# motor_driver_current_sensor.net
KiCad netlist of a schematic drawn in Altium Designer
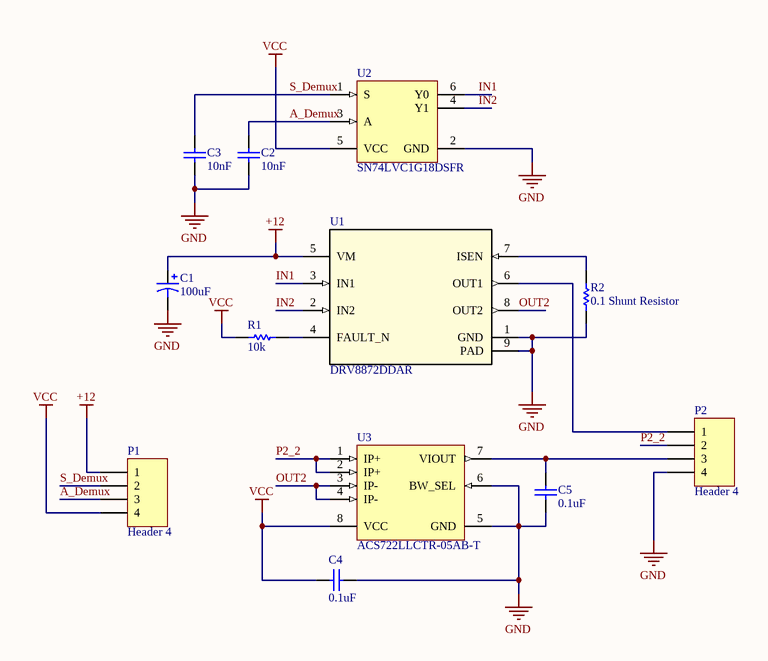
[diagram p0: motor_driver_current_sensor.SchDoc]

(export (version "E")
  (design (tool "Eeschema 10.0.6"))
  (components
    (comp (ref "C1")
      (value "100uF")
      (footprint "RB7.6-15")
      (description "Polarized Capacitor (Radial)")
      (fields (field (name "PUBLISHER") "Altium Limited"))
      (libsource (lib "Miscellaneous Devices") (part "Cap Pol1"))
    )
    (comp (ref "C2")
      (value "10nF")
      (footprint "CAPC0805(2012)145_L")
      (description "0805 (2012 Metric) Chip Capacitor")
      (libsource (lib "Altium Content Vault") (part "CAP_5"))
    )
    (comp (ref "C3")
      (value "10nF")
      (footprint "CAPC0805(2012)145_L")
      (description "0805 (2012 Metric) Chip Capacitor")
      (libsource (lib "Altium Content Vault") (part "CAP_5"))
    )
    (comp (ref "C4")
      (value "0.1uF")
      (footprint "RAD-0.3")
      (description "Capacitor")
      (fields (field (name "PUBLISHER") "Altium Limited"))
      (libsource (lib "Miscellaneous Devices") (part "Cap"))
    )
    (comp (ref "C5")
      (value "0.1uF")
      (footprint "RAD-0.3")
      (description "Capacitor")
      (fields (field (name "PUBLISHER") "Altium Limited"))
      (libsource (lib "Miscellaneous Devices") (part "Cap"))
    )
    (comp (ref "P1")
      (value "Header 4")
      (footprint "HDR1X4")
      (description "Header, 4-Pin")
      (fields (field (name "PUBLISHER") "Altium Limited"))
      (libsource (lib "Miscellaneous Connectors") (part "Header 4"))
    )
    (comp (ref "P2")
      (value "Header 4")
      (footprint "HDR1X4")
      (description "Header, 4-Pin")
      (fields (field (name "PUBLISHER") "Altium Limited"))
      (libsource (lib "Miscellaneous Connectors") (part "Header 4"))
    )
    (comp (ref "R1")
      (value "10k")
      (footprint "RESC1608X55X30LL20T20")
      (description "Pull up resistor for FAULT_IN")
      (fields (field (name "PART NUMBER") "ERA3AEB334V") (field (name "MANUFACTURER") "Panasonic"))
      (libsource (lib "Altium Content Vault") (part "RES"))
    )
    (comp (ref "R2")
      (value "0.1 Shunt Resistor")
      (footprint "RESC2512(6432)_L")
      (description "2512 (6432 Metric) Chip Resistor")
      (libsource (lib "Altium Content Vault") (part "RES_3"))
    )
    (comp (ref "U1")
      (value "DRV8872DDAR")
      (footprint "DDA0008H_N")
      (description "Imported")
      (fields
        (field (name "ALTERNATE_PARTNUMBER") "DRV8872DDA")
        (field (name "MANUFACTURER") "Texas Instruments")
      )
      (libsource (lib "Custom_Lib") (part "DRV8872DDAR"))
    )
    (comp (ref "U2")
      (value "SN74LVC1G18DSFR")
      (footprint "DSF0006A_V")
      (description "One of Two Noninverting Demultiplexer with 3-State Deselected Output, DSF0006A, LARGE T&R")
      (fields
        (field (name "GENERIC PART NUMBER") "SN74LVC1G18")
        (field (name "MANUFACTURER") "Texas Instruments")
      )
      (libsource (lib "Altium Content Vault") (part "TI-SN74LVC1G18-6"))
    )
    (comp (ref "U3")
      (value "ACS722LLCTR-05AB-T")
      (footprint "ALEG-LC-8_V")
      (libsource (lib "Altium Content Vault") (part "ALEG-ACS722-SOIC-8"))
    )
  )
  (nets
    (net (code "1") (name "+12") (class "Default")
      (node (ref "C1") (pin "1") (pinfunction "1_1") (pintype "passive"))
      (node (ref "P1") (pin "1") (pinfunction "1_1") (pintype "passive"))
      (node (ref "U1") (pin "5") (pinfunction "VM_5") (pintype "power_in"))
    )
    (net (code "2") (name "/A_Demux") (class "Default")
      (node (ref "C2") (pin "2") (pinfunction "2_2") (pintype "passive"))
      (node (ref "P1") (pin "3") (pinfunction "3_3") (pintype "passive"))
      (node (ref "U2") (pin "3") (pinfunction "A_3") (pintype "input"))
    )
    (net (code "3") (name "/IN1") (class "Default")
      (node (ref "U1") (pin "3") (pinfunction "IN1_3") (pintype "input"))
      (node (ref "U2") (pin "6") (pinfunction "Y0_6") (pintype "tri_state"))
    )
    (net (code "4") (name "/IN2") (class "Default")
      (node (ref "U1") (pin "2") (pinfunction "IN2_2") (pintype "input"))
      (node (ref "U2") (pin "4") (pinfunction "Y1_4") (pintype "tri_state"))
    )
    (net (code "5") (name "/OUT2") (class "Default")
      (node (ref "U1") (pin "8") (pinfunction "OUT2_8") (pintype "output"))
      (node (ref "U3") (pin "3") (pinfunction "IP-_3") (pintype "input"))
      (node (ref "U3") (pin "4") (pinfunction "IP-_4") (pintype "input"))
    )
    (net (code "6") (name "/P2_2") (class "Default")
      (node (ref "P2") (pin "2") (pinfunction "2_2") (pintype "passive"))
      (node (ref "U3") (pin "1") (pinfunction "IP+_1") (pintype "input"))
      (node (ref "U3") (pin "2") (pinfunction "IP+_2") (pintype "input"))
    )
    (net (code "7") (name "/S_Demux") (class "Default")
      (node (ref "C3") (pin "2") (pinfunction "2_2") (pintype "passive"))
      (node (ref "P1") (pin "2") (pinfunction "2_2") (pintype "passive"))
      (node (ref "U2") (pin "1") (pinfunction "S_1") (pintype "input"))
    )
    (net (code "8") (name "GND") (class "Default")
      (node (ref "C1") (pin "2") (pinfunction "2_2") (pintype "passive"))
      (node (ref "C2") (pin "1") (pinfunction "1_1") (pintype "passive"))
      (node (ref "C3") (pin "1") (pinfunction "1_1") (pintype "passive"))
      (node (ref "C4") (pin "2") (pinfunction "2_2") (pintype "passive"))
      (node (ref "C5") (pin "1") (pinfunction "1_1") (pintype "passive"))
      (node (ref "P2") (pin "4") (pinfunction "4_4") (pintype "passive"))
      (node (ref "R2") (pin "1") (pinfunction "1_1") (pintype "passive"))
      (node (ref "U1") (pin "1") (pinfunction "GND_1") (pintype "power_in"))
      (node (ref "U1") (pin "9") (pinfunction "PAD_9") (pintype "power_in"))
      (node (ref "U2") (pin "2") (pinfunction "GND_2") (pintype "power_in"))
      (node (ref "U3") (pin "5") (pinfunction "GND_5") (pintype "power_in"))
      (node (ref "U3") (pin "6") (pinfunction "BW_SEL_6") (pintype "input"))
    )
    (net (code "9") (name "Net-(U1-FAULT_N)") (class "Default")
      (node (ref "R1") (pin "2") (pinfunction "2_2") (pintype "passive"))
      (node (ref "U1") (pin "4") (pinfunction "FAULT_N_4") (pintype "open_collector"))
    )
    (net (code "10") (name "Net-(U1-ISEN)") (class "Default")
      (node (ref "R2") (pin "2") (pinfunction "2_2") (pintype "passive"))
      (node (ref "U1") (pin "7") (pinfunction "ISEN_7") (pintype "input"))
    )
    (net (code "11") (name "Net-(U1-OUT1)") (class "Default")
      (node (ref "P2") (pin "1") (pinfunction "1_1") (pintype "passive"))
      (node (ref "U1") (pin "6") (pinfunction "OUT1_6") (pintype "output"))
    )
    (net (code "12") (name "Net-(U3-VIOUT)") (class "Default")
      (node (ref "C5") (pin "2") (pinfunction "2_2") (pintype "passive"))
      (node (ref "P2") (pin "3") (pinfunction "3_3") (pintype "passive"))
      (node (ref "U3") (pin "7") (pinfunction "VIOUT_7") (pintype "output"))
    )
    (net (code "13") (name "VCC") (class "Default")
      (node (ref "C4") (pin "1") (pinfunction "1_1") (pintype "passive"))
      (node (ref "P1") (pin "4") (pinfunction "4_4") (pintype "passive"))
      (node (ref "R1") (pin "1") (pinfunction "1_1") (pintype "passive"))
      (node (ref "U2") (pin "5") (pinfunction "VCC_5") (pintype "power_in"))
      (node (ref "U3") (pin "8") (pinfunction "VCC_8") (pintype "power_in"))
    )
  )
)
